# schaltplan_rsu-2.net
KiCad netlist of a schematic drawn in EAGLE
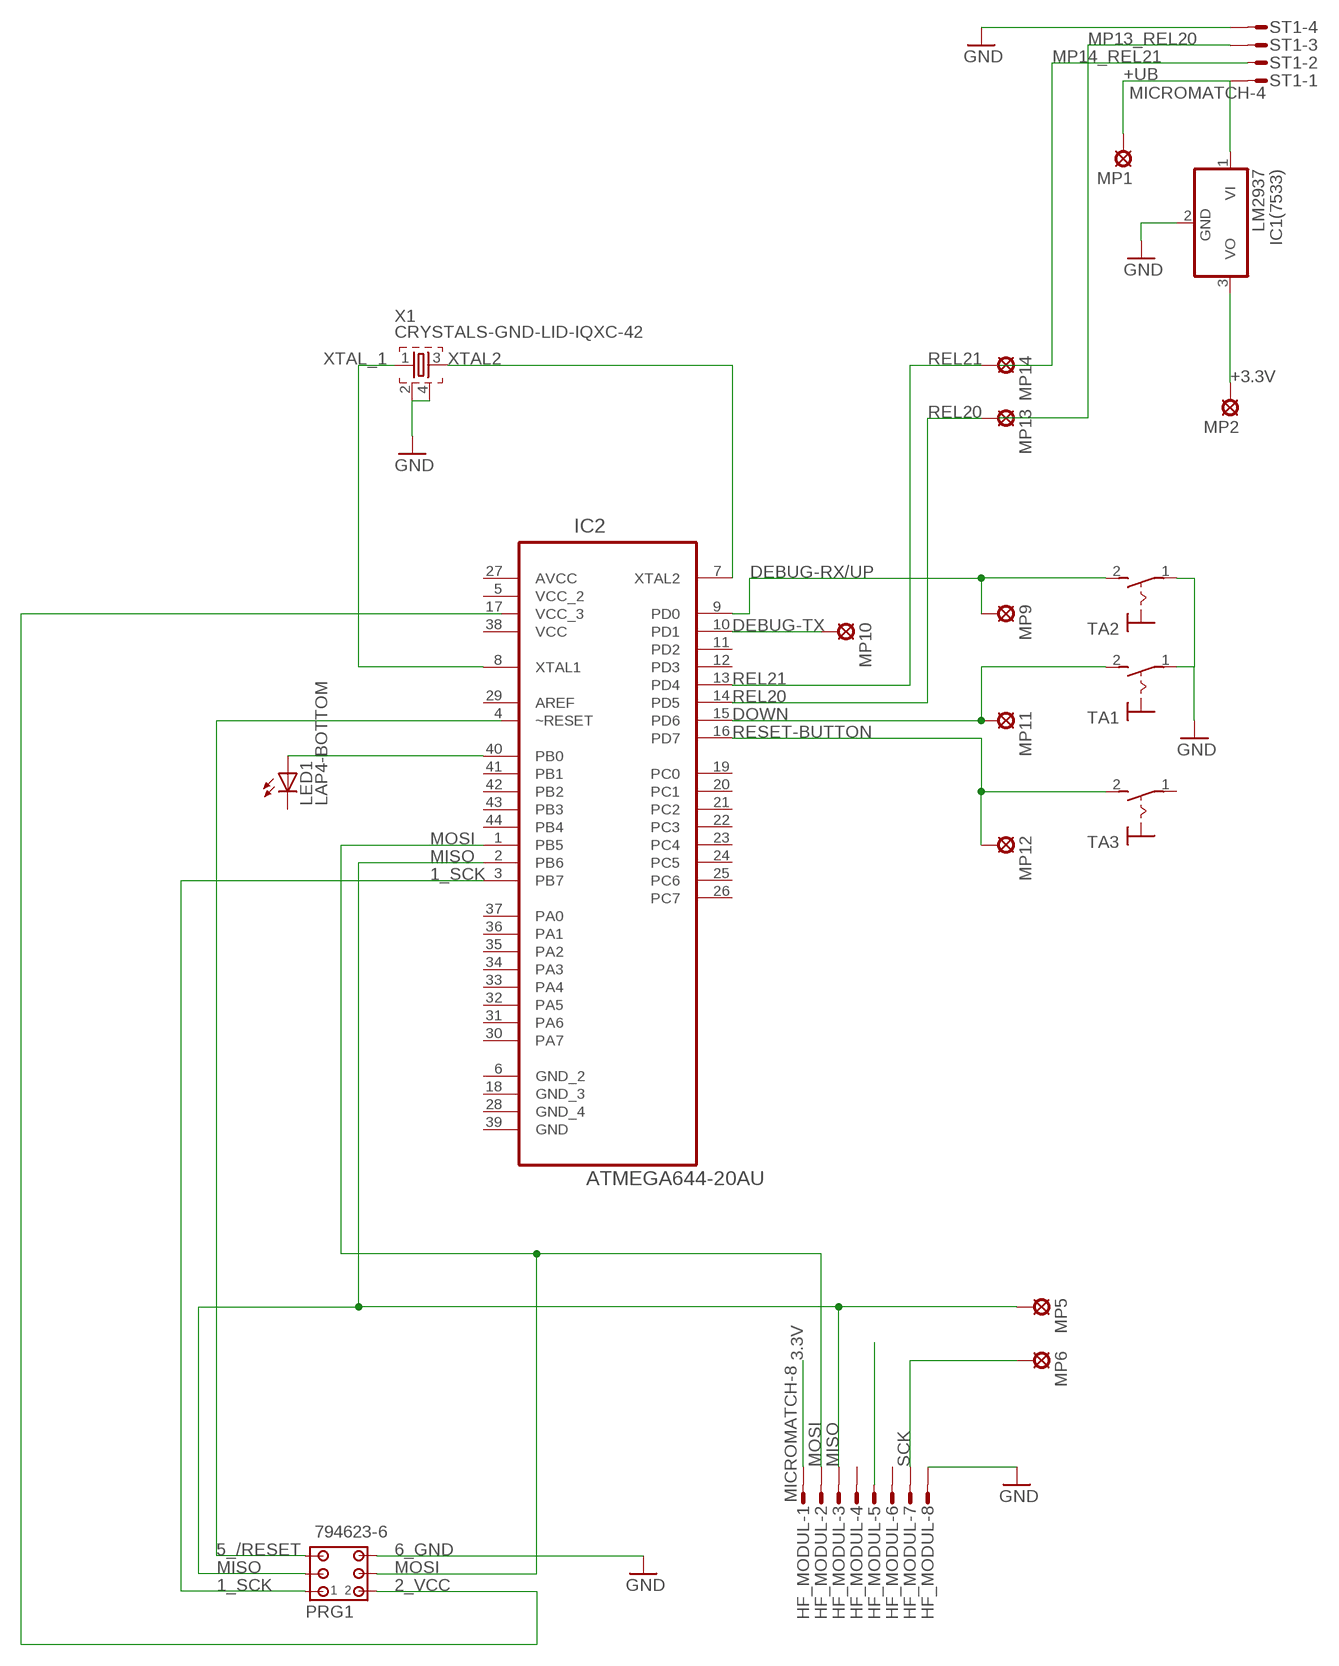
[diagram p0: schematic, sheet 1]

(export (version "E")
  (design (tool "Eeschema 10.0.6"))
  (components
    (comp (ref "HF_MODUL")
      (value "MICROMATCH-8")
      (footprint "eagle-import:MICROMATCH-8")
      (fields (field (name "MF") "FARNELL") (field (name "MPN") "7-215464-8"))
      (libsource (lib "eagle-import") (part "MICROMATCH-8"))
    )
    (comp (ref "IC1(7533)")
      (value "LM2937")
      (footprint "eagle-import:TO263-3")
      (libsource (lib "eagle-import") (part "LM2937"))
    )
    (comp (ref "IC2")
      (value "ATMEGA644-20AU")
      (footprint "eagle-import:QFP80P1200X1200X120-44N")
      (libsource (lib "eagle-import") (part "ATMEGA644-20AU"))
    )
    (comp (ref "LED1")
      (value "LAP4-BOTTOM")
      (footprint "eagle-import:P47F-BOTTOM")
      (libsource (lib "eagle-import") (part "P4-BOTTOMLA"))
    )
    (comp (ref "MP1")
      (value "LSP11")
      (footprint "eagle-import:LSP11")
      (libsource (lib "eagle-import") (part "LSP11"))
    )
    (comp (ref "MP2")
      (value "LSP11")
      (footprint "eagle-import:LSP11")
      (libsource (lib "eagle-import") (part "LSP11"))
    )
    (comp (ref "MP5")
      (value "LSP11")
      (footprint "eagle-import:LSP11")
      (libsource (lib "eagle-import") (part "LSP11"))
    )
    (comp (ref "MP6")
      (value "LSP11")
      (footprint "eagle-import:LSP11")
      (libsource (lib "eagle-import") (part "LSP11"))
    )
    (comp (ref "MP9")
      (value "LSP11")
      (footprint "eagle-import:LSP11")
      (libsource (lib "eagle-import") (part "LSP11"))
    )
    (comp (ref "MP10")
      (value "LSP11")
      (footprint "eagle-import:LSP11")
      (libsource (lib "eagle-import") (part "LSP11"))
    )
    (comp (ref "MP11")
      (value "LSP11")
      (footprint "eagle-import:LSP11")
      (libsource (lib "eagle-import") (part "LSP11"))
    )
    (comp (ref "MP12")
      (value "LSP11")
      (footprint "eagle-import:LSP11")
      (libsource (lib "eagle-import") (part "LSP11"))
    )
    (comp (ref "MP13")
      (value "LSP11")
      (footprint "eagle-import:LSP11")
      (libsource (lib "eagle-import") (part "LSP11"))
    )
    (comp (ref "MP14")
      (value "LSP11")
      (footprint "eagle-import:LSP11")
      (libsource (lib "eagle-import") (part "LSP11"))
    )
    (comp (ref "PRG1")
      (value "794623-6")
      (footprint "eagle-import:794623-6")
      (libsource (lib "eagle-import") (part "794623-6"))
    )
    (comp (ref "ST1")
      (value "MICROMATCH-4")
      (footprint "eagle-import:MICROMATCH-4")
      (fields (field (name "MPN") "7-215464-4"))
      (libsource (lib "eagle-import") (part "MICROMATCH-4"))
    )
    (comp (ref "TA1")
      (value "MS243")
      (footprint "eagle-import:MS243")
      (libsource (lib "eagle-import") (part "MS243"))
    )
    (comp (ref "TA2")
      (value "MS243")
      (footprint "eagle-import:MS243")
      (libsource (lib "eagle-import") (part "MS243"))
    )
    (comp (ref "TA3")
      (value "MS243")
      (footprint "eagle-import:MS243")
      (libsource (lib "eagle-import") (part "MS243"))
    )
    (comp (ref "X1")
      (value "CRYSTALS-GND-LID-IQXC-42")
      (footprint "eagle-import:2.0X1.6-4-PAD")
      (libsource (lib "eagle-import") (part "CRYSTALS-GND-LID-IQXC-42"))
    )
  )
  (nets
    (net (code "1") (name "/+3.3V") (class "Default")
      (node (ref "IC1(7533)") (pin "3") (pinfunction "VO_3") (pintype "passive"))
      (node (ref "MP2") (pin "MP") (pinfunction "MP_MP") (pintype "passive"))
    )
    (net (code "2") (name "/+UB") (class "Default")
      (node (ref "IC1(7533)") (pin "1") (pinfunction "VI_1") (pintype "input"))
      (node (ref "MP1") (pin "MP") (pinfunction "MP_MP") (pintype "passive"))
      (node (ref "ST1") (pin "1") (pinfunction "S_1") (pintype "passive"))
    )
    (net (code "3") (name "/1_SCK") (class "Default")
      (node (ref "IC2") (pin "3") (pinfunction "PB7_3") (pintype "bidirectional"))
      (node (ref "PRG1") (pin "1") (pinfunction "1_1") (pintype "passive"))
    )
    (net (code "4") (name "/2_VCC") (class "Default")
      (node (ref "PRG1") (pin "2") (pinfunction "2_2") (pintype "passive"))
    )
    (net (code "5") (name "/3.3V") (class "Default")
      (node (ref "HF_MODUL") (pin "1") (pinfunction "S_1") (pintype "passive"))
    )
    (net (code "6") (name "/5_{slash}RESET") (class "Default")
      (node (ref "PRG1") (pin "5") (pinfunction "5_5") (pintype "passive"))
    )
    (net (code "7") (name "/AVCC") (class "Default")
      (node (ref "IC2") (pin "27") (pinfunction "AVCC_27") (pintype "power_in"))
    )
    (net (code "8") (name "/DEBUG-RX{slash}UP") (class "Default")
      (node (ref "IC2") (pin "9") (pinfunction "PD0_9") (pintype "bidirectional"))
      (node (ref "MP9") (pin "MP") (pinfunction "MP_MP") (pintype "passive"))
      (node (ref "TA2") (pin "2") (pinfunction "S_2") (pintype "passive"))
    )
    (net (code "9") (name "/DEBUG-TX") (class "Default")
      (node (ref "IC2") (pin "10") (pinfunction "PD1_10") (pintype "bidirectional"))
      (node (ref "MP10") (pin "MP") (pinfunction "MP_MP") (pintype "passive"))
    )
    (net (code "10") (name "/DOWN") (class "Default")
      (node (ref "IC2") (pin "15") (pinfunction "PD6_15") (pintype "bidirectional"))
      (node (ref "MP11") (pin "MP") (pinfunction "MP_MP") (pintype "passive"))
      (node (ref "TA1") (pin "2") (pinfunction "S_2") (pintype "passive"))
    )
    (net (code "11") (name "/MISO") (class "Default")
      (node (ref "HF_MODUL") (pin "3") (pinfunction "S_3") (pintype "passive"))
      (node (ref "IC2") (pin "2") (pinfunction "PB6_2") (pintype "bidirectional"))
      (node (ref "MP5") (pin "MP") (pinfunction "MP_MP") (pintype "passive"))
      (node (ref "PRG1") (pin "3") (pinfunction "3_3") (pintype "passive"))
    )
    (net (code "12") (name "/MOSI") (class "Default")
      (node (ref "HF_MODUL") (pin "2") (pinfunction "S_2") (pintype "passive"))
      (node (ref "IC2") (pin "1") (pinfunction "PB5_1") (pintype "bidirectional"))
      (node (ref "PRG1") (pin "4") (pinfunction "4_4") (pintype "passive"))
    )
    (net (code "13") (name "/MP13_REL20") (class "Default")
      (node (ref "ST1") (pin "3") (pinfunction "S_3") (pintype "passive"))
    )
    (net (code "15") (name "/REL20") (class "Default")
      (node (ref "IC2") (pin "14") (pinfunction "PD5_14") (pintype "bidirectional"))
      (node (ref "MP13") (pin "MP") (pinfunction "MP_MP") (pintype "passive"))
    )
    (net (code "16") (name "/REL21") (class "Default")
      (node (ref "IC2") (pin "13") (pinfunction "PD4_13") (pintype "bidirectional"))
      (node (ref "MP14") (pin "MP") (pinfunction "MP_MP") (pintype "passive"))
    )
    (net (code "17") (name "/RESET-BUTTON") (class "Default")
      (node (ref "IC2") (pin "16") (pinfunction "PD7_16") (pintype "bidirectional"))
      (node (ref "MP12") (pin "MP") (pinfunction "MP_MP") (pintype "passive"))
      (node (ref "TA3") (pin "2") (pinfunction "S_2") (pintype "passive"))
    )
    (net (code "18") (name "/SCK") (class "Default")
      (node (ref "HF_MODUL") (pin "7") (pinfunction "S_7") (pintype "passive"))
      (node (ref "MP6") (pin "MP") (pinfunction "MP_MP") (pintype "passive"))
    )
    (net (code "19") (name "/VCC") (class "Default")
      (node (ref "IC2") (pin "38") (pinfunction "VCC_38") (pintype "power_in"))
    )
    (net (code "20") (name "/VCC_2") (class "Default")
      (node (ref "IC2") (pin "5") (pinfunction "VCC_2_5") (pintype "power_in"))
    )
    (net (code "21") (name "/VCC_3") (class "Default")
      (node (ref "IC2") (pin "17") (pinfunction "VCC_3_17") (pintype "power_in"))
    )
    (net (code "22") (name "/XTAL2") (class "Default")
      (node (ref "IC2") (pin "7") (pinfunction "XTAL2_7") (pintype "output"))
      (node (ref "X1") (pin "3") (pinfunction "3_3") (pintype "passive"))
    )
    (net (code "23") (name "/XTAL_1") (class "Default")
      (node (ref "IC2") (pin "8") (pinfunction "XTAL1_8") (pintype "input"))
      (node (ref "X1") (pin "1") (pinfunction "1_1") (pintype "passive"))
    )
    (net (code "24") (name "GND") (class "Default")
      (node (ref "HF_MODUL") (pin "8") (pinfunction "S_8") (pintype "passive"))
      (node (ref "IC1(7533)") (pin "2") (pinfunction "GND_2") (pintype "passive"))
      (node (ref "PRG1") (pin "6") (pinfunction "6_6") (pintype "passive"))
      (node (ref "ST1") (pin "4") (pinfunction "S_4") (pintype "passive"))
      (node (ref "TA1") (pin "1") (pinfunction "P_1") (pintype "passive"))
      (node (ref "TA2") (pin "1") (pinfunction "P_1") (pintype "passive"))
      (node (ref "X1") (pin "2") (pinfunction "2_2") (pintype "passive"))
      (node (ref "X1") (pin "4") (pinfunction "4_4") (pintype "passive"))
    )
    (net (code "25") (name "Net-(IC2-PB0)") (class "Default")
      (node (ref "IC2") (pin "40") (pinfunction "PB0_40") (pintype "bidirectional"))
      (node (ref "LED1") (pin "A") (pinfunction "A_A") (pintype "passive"))
    )
    (net (code "26") (name "unconnected-(HF_MODULD-S-Pad4)") (class "Default")
      (node (ref "HF_MODUL") (pin "4") (pinfunction "S_4") (pintype "passive"))
    )
    (net (code "27") (name "unconnected-(HF_MODULE-S-Pad5)") (class "Default")
      (node (ref "HF_MODUL") (pin "5") (pinfunction "S_5") (pintype "passive"))
    )
    (net (code "28") (name "unconnected-(HF_MODULF-S-Pad6)") (class "Default")
      (node (ref "HF_MODUL") (pin "6") (pinfunction "S_6") (pintype "passive"))
    )
    (net (code "29") (name "unconnected-(IC2-AREF-Pad29)") (class "Default")
      (node (ref "IC2") (pin "29") (pinfunction "AREF_29") (pintype "input"))
    )
    (net (code "30") (name "unconnected-(IC2-GND-Pad39)") (class "Default")
      (node (ref "IC2") (pin "39") (pinfunction "GND_39") (pintype "passive"))
    )
    (net (code "31") (name "unconnected-(IC2-GND_2-Pad6)") (class "Default")
      (node (ref "IC2") (pin "6") (pinfunction "GND_2_6") (pintype "passive"))
    )
    (net (code "32") (name "unconnected-(IC2-GND_3-Pad18)") (class "Default")
      (node (ref "IC2") (pin "18") (pinfunction "GND_3_18") (pintype "passive"))
    )
    (net (code "33") (name "unconnected-(IC2-GND_4-Pad28)") (class "Default")
      (node (ref "IC2") (pin "28") (pinfunction "GND_4_28") (pintype "passive"))
    )
    (net (code "34") (name "unconnected-(IC2-PA0-Pad37)") (class "Default")
      (node (ref "IC2") (pin "37") (pinfunction "PA0_37") (pintype "bidirectional"))
    )
    (net (code "35") (name "unconnected-(IC2-PA1-Pad36)") (class "Default")
      (node (ref "IC2") (pin "36") (pinfunction "PA1_36") (pintype "bidirectional"))
    )
    (net (code "36") (name "unconnected-(IC2-PA2-Pad35)") (class "Default")
      (node (ref "IC2") (pin "35") (pinfunction "PA2_35") (pintype "bidirectional"))
    )
    (net (code "37") (name "unconnected-(IC2-PA3-Pad34)") (class "Default")
      (node (ref "IC2") (pin "34") (pinfunction "PA3_34") (pintype "bidirectional"))
    )
    (net (code "38") (name "unconnected-(IC2-PA4-Pad33)") (class "Default")
      (node (ref "IC2") (pin "33") (pinfunction "PA4_33") (pintype "bidirectional"))
    )
    (net (code "39") (name "unconnected-(IC2-PA5-Pad32)") (class "Default")
      (node (ref "IC2") (pin "32") (pinfunction "PA5_32") (pintype "bidirectional"))
    )
    (net (code "40") (name "unconnected-(IC2-PA6-Pad31)") (class "Default")
      (node (ref "IC2") (pin "31") (pinfunction "PA6_31") (pintype "bidirectional"))
    )
    (net (code "41") (name "unconnected-(IC2-PA7-Pad30)") (class "Default")
      (node (ref "IC2") (pin "30") (pinfunction "PA7_30") (pintype "bidirectional"))
    )
    (net (code "42") (name "unconnected-(IC2-PB1-Pad41)") (class "Default")
      (node (ref "IC2") (pin "41") (pinfunction "PB1_41") (pintype "bidirectional"))
    )
    (net (code "43") (name "unconnected-(IC2-PB2-Pad42)") (class "Default")
      (node (ref "IC2") (pin "42") (pinfunction "PB2_42") (pintype "bidirectional"))
    )
    (net (code "44") (name "unconnected-(IC2-PB3-Pad43)") (class "Default")
      (node (ref "IC2") (pin "43") (pinfunction "PB3_43") (pintype "bidirectional"))
    )
    (net (code "45") (name "unconnected-(IC2-PB4-Pad44)") (class "Default")
      (node (ref "IC2") (pin "44") (pinfunction "PB4_44") (pintype "bidirectional"))
    )
    (net (code "46") (name "unconnected-(IC2-PC0-Pad19)") (class "Default")
      (node (ref "IC2") (pin "19") (pinfunction "PC0_19") (pintype "bidirectional"))
    )
    (net (code "47") (name "unconnected-(IC2-PC1-Pad20)") (class "Default")
      (node (ref "IC2") (pin "20") (pinfunction "PC1_20") (pintype "bidirectional"))
    )
    (net (code "48") (name "unconnected-(IC2-PC2-Pad21)") (class "Default")
      (node (ref "IC2") (pin "21") (pinfunction "PC2_21") (pintype "bidirectional"))
    )
    (net (code "49") (name "unconnected-(IC2-PC3-Pad22)") (class "Default")
      (node (ref "IC2") (pin "22") (pinfunction "PC3_22") (pintype "bidirectional"))
    )
    (net (code "50") (name "unconnected-(IC2-PC4-Pad23)") (class "Default")
      (node (ref "IC2") (pin "23") (pinfunction "PC4_23") (pintype "bidirectional"))
    )
    (net (code "51") (name "unconnected-(IC2-PC5-Pad24)") (class "Default")
      (node (ref "IC2") (pin "24") (pinfunction "PC5_24") (pintype "bidirectional"))
    )
    (net (code "52") (name "unconnected-(IC2-PC6-Pad25)") (class "Default")
      (node (ref "IC2") (pin "25") (pinfunction "PC6_25") (pintype "bidirectional"))
    )
    (net (code "53") (name "unconnected-(IC2-PC7-Pad26)") (class "Default")
      (node (ref "IC2") (pin "26") (pinfunction "PC7_26") (pintype "bidirectional"))
    )
    (net (code "54") (name "unconnected-(IC2-PD2-Pad11)") (class "Default")
      (node (ref "IC2") (pin "11") (pinfunction "PD2_11") (pintype "bidirectional"))
    )
    (net (code "55") (name "unconnected-(IC2-PD3-Pad12)") (class "Default")
      (node (ref "IC2") (pin "12") (pinfunction "PD3_12") (pintype "bidirectional"))
    )
    (net (code "56") (name "unconnected-(IC2-~{RESET}-Pad4)") (class "Default")
      (node (ref "IC2") (pin "4") (pinfunction "~{RESET}_4") (pintype "input"))
    )
    (net (code "57") (name "unconnected-(LED1-PadC)") (class "Default")
      (node (ref "LED1") (pin "C") (pinfunction "C_C") (pintype "passive"))
    )
    (net (code "58") (name "unconnected-(ST1B-S-Pad2)") (class "Default")
      (node (ref "ST1") (pin "2") (pinfunction "S_2") (pintype "passive"))
    )
    (net (code "59") (name "unconnected-(TA3-P-Pad1)") (class "Default")
      (node (ref "TA3") (pin "1") (pinfunction "P_1") (pintype "passive"))
    )
  )
)
